# Atari_Controller.net
KiCad netlist of a schematic drawn in Altium Designer
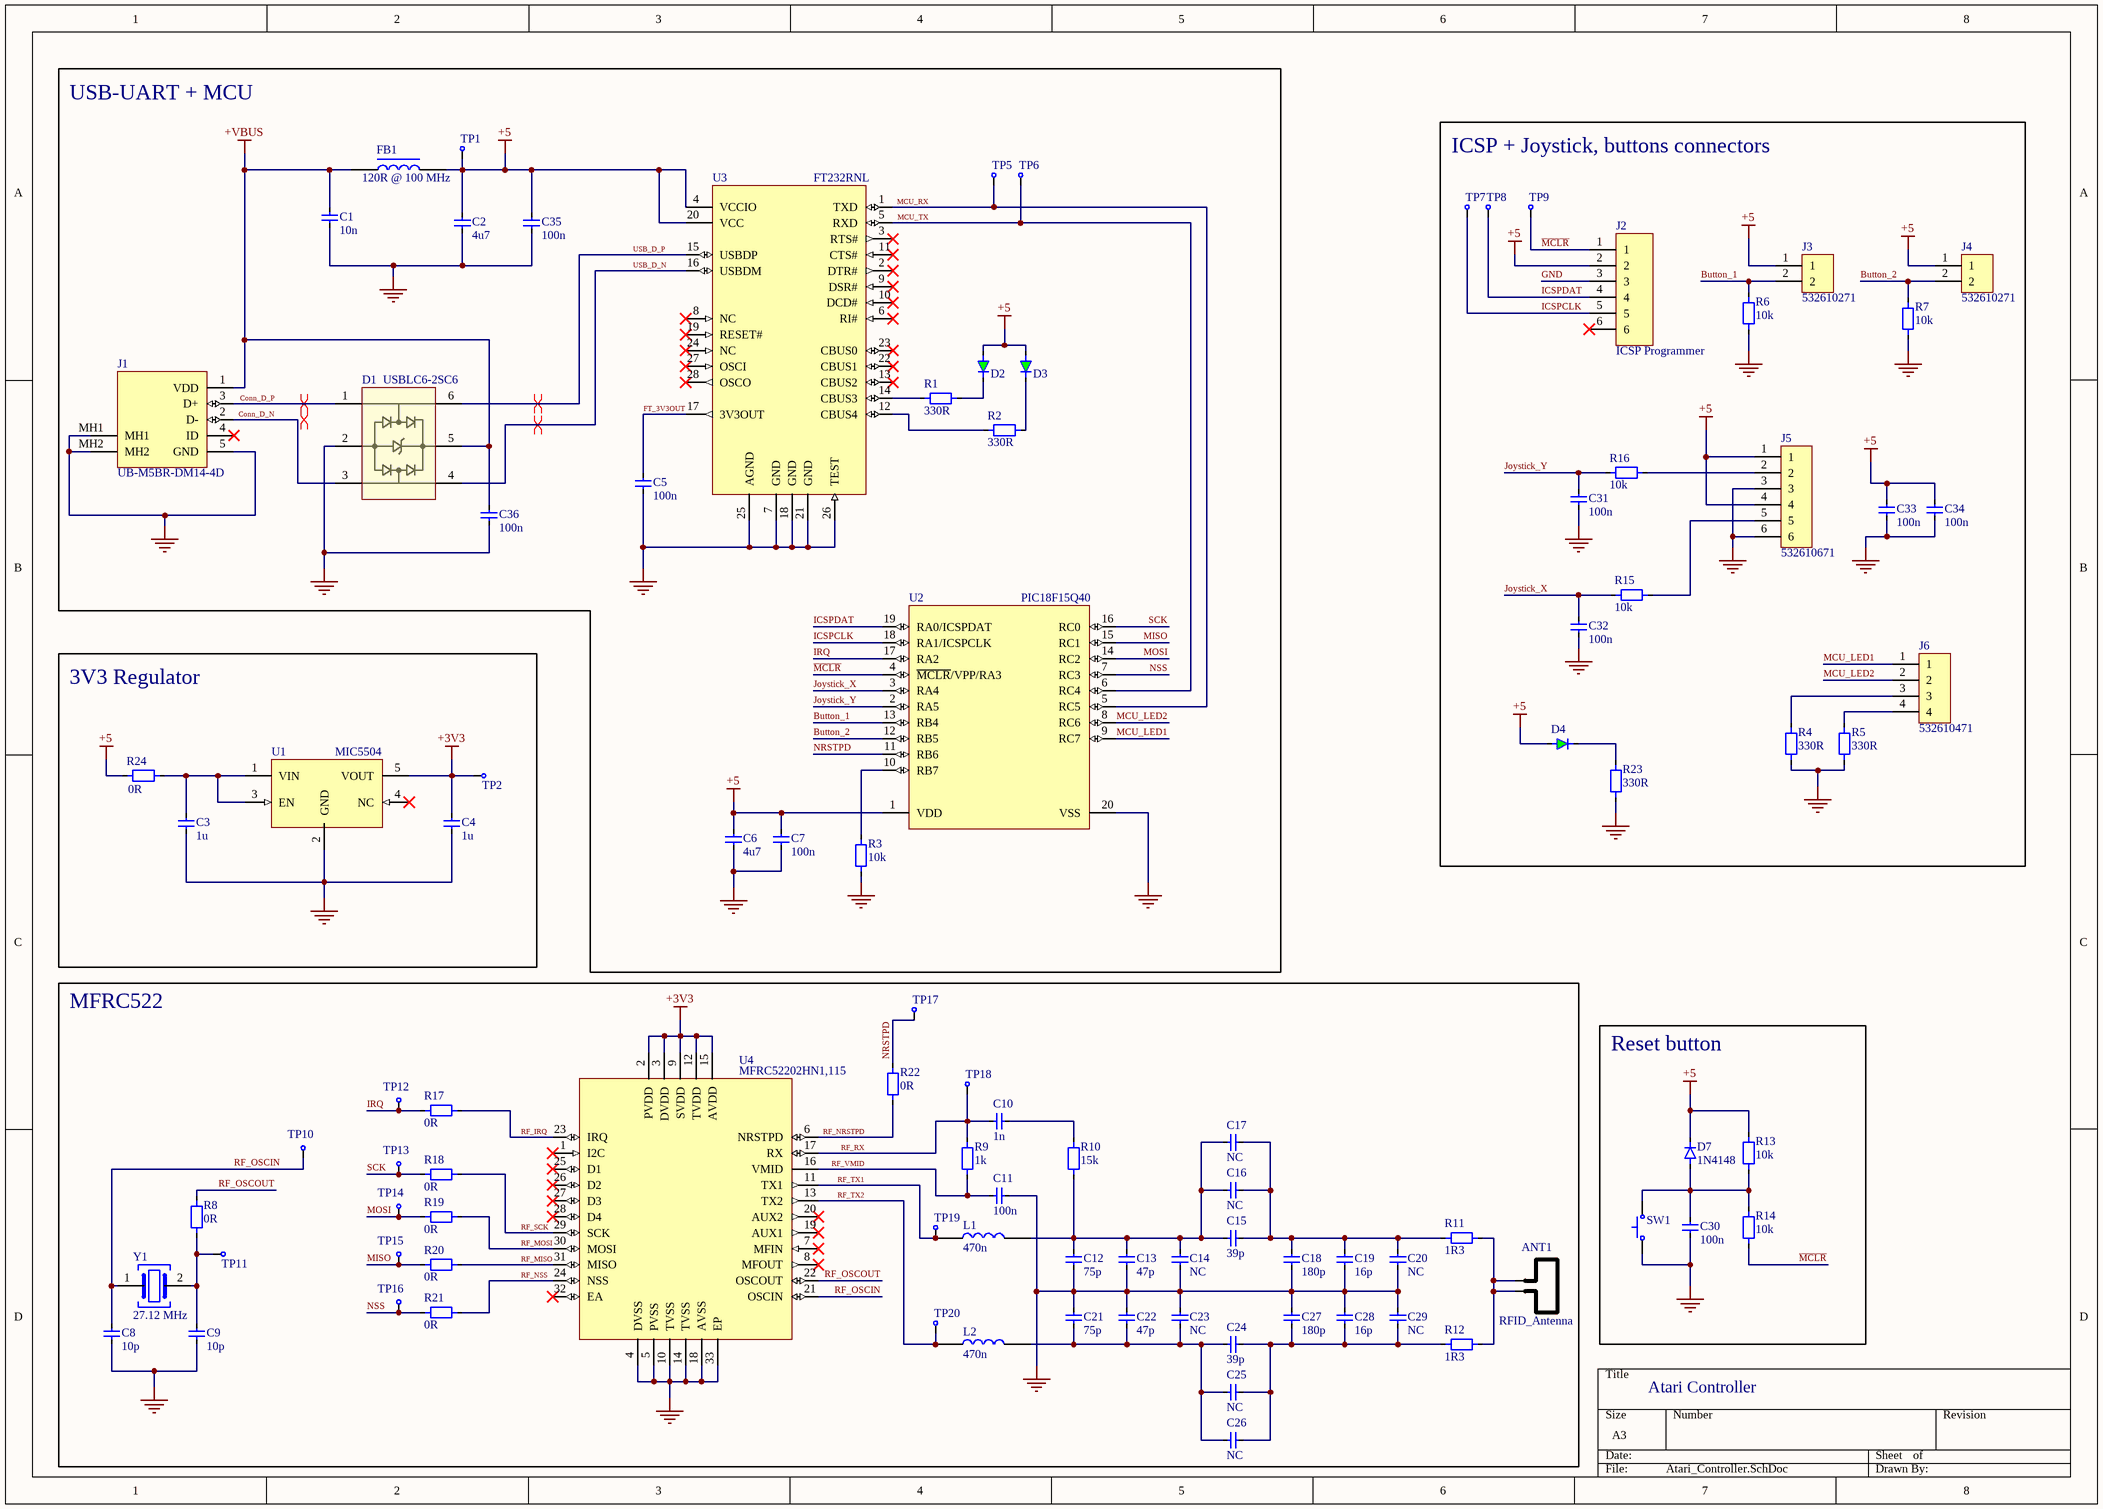
[diagram p0: Atari_Controller.SchDoc]

(export (version "E")
  (design (tool "Eeschema 10.0.6"))
  (components
    (comp (ref "ANT1")
      (value "RFID_Antenna")
      (footprint "RFID_Antenna")
      (description "Matching for MRFC522")
      (libsource (lib "Schematics_Connectors") (part "RFID_Antenna"))
    )
    (comp (ref "C1")
      (value "10n")
      (footprint "CAP_0603")
      (description "Capacitor SMD 0603 16V")
      (libsource (lib "Schematics_Passives") (part "CAP_0603_16V"))
    )
    (comp (ref "C2")
      (value "4u7")
      (footprint "CAP_0603")
      (description "Capacitor SMD 0603 16V")
      (libsource (lib "Schematics_Passives") (part "CAP_0603_16V"))
    )
    (comp (ref "C3")
      (value "1u")
      (footprint "CAP_0603")
      (description "Capacitor SMD 0603 16V")
      (libsource (lib "Schematics_Passives") (part "CAP_0603_16V"))
    )
    (comp (ref "C4")
      (value "1u")
      (footprint "CAP_0603")
      (description "Capacitor SMD 0603 16V")
      (libsource (lib "Schematics_Passives") (part "CAP_0603_16V"))
    )
    (comp (ref "C5")
      (value "100n")
      (footprint "CAP_0603")
      (description "Capacitor SMD 0603 10V")
      (libsource (lib "Schematics_Passives") (part "CAP_0603_10V"))
    )
    (comp (ref "C6")
      (value "4u7")
      (footprint "CAP_0603")
      (description "Capacitor SMD 0603 16V")
      (libsource (lib "Schematics_Passives") (part "CAP_0603_16V"))
    )
    (comp (ref "C7")
      (value "100n")
      (footprint "CAP_0603")
      (description "Capacitor SMD 0603 16V")
      (libsource (lib "Schematics_Passives") (part "CAP_0603_16V"))
    )
    (comp (ref "C8")
      (value "10p")
      (footprint "CAP_0603")
      (description "Capacitor SMD 0603 16V")
      (libsource (lib "Schematics_Passives") (part "CAP_0603_16V"))
    )
    (comp (ref "C9")
      (value "10p")
      (footprint "CAP_0603")
      (description "Capacitor SMD 0603 16V")
      (libsource (lib "Schematics_Passives") (part "CAP_0603_16V"))
    )
    (comp (ref "C10")
      (value "1n")
      (footprint "CAP_0603")
      (description "Capacitor SMD 0603 16V")
      (libsource (lib "Schematics_Passives") (part "CAP_0603_16V"))
    )
    (comp (ref "C11")
      (value "100n")
      (footprint "CAP_0603")
      (description "Capacitor SMD 0603 16V")
      (libsource (lib "Schematics_Passives") (part "CAP_0603_16V"))
    )
    (comp (ref "C12")
      (value "75p")
      (footprint "CAP_0603")
      (description "Capacitor SMD 0603 16V")
      (libsource (lib "Schematics_Passives") (part "CAP_0603_16V"))
    )
    (comp (ref "C13")
      (value "47p")
      (footprint "CAP_0603")
      (description "Capacitor SMD 0603 16V")
      (libsource (lib "Schematics_Passives") (part "CAP_0603_16V"))
    )
    (comp (ref "C14")
      (value "NC")
      (footprint "CAP_0603")
      (description "Capacitor SMD 0603 16V")
      (libsource (lib "Schematics_Passives") (part "CAP_0603_16V"))
    )
    (comp (ref "C15")
      (value "39p")
      (footprint "CAP_0603")
      (description "Capacitor SMD 0603 16V")
      (libsource (lib "Schematics_Passives") (part "CAP_0603_16V"))
    )
    (comp (ref "C16")
      (value "NC")
      (footprint "CAP_0603")
      (description "Capacitor SMD 0603 16V")
      (libsource (lib "Schematics_Passives") (part "CAP_0603_16V"))
    )
    (comp (ref "C17")
      (value "NC")
      (footprint "CAP_0603")
      (description "Capacitor SMD 0603 16V")
      (libsource (lib "Schematics_Passives") (part "CAP_0603_16V"))
    )
    (comp (ref "C18")
      (value "180p")
      (footprint "CAP_0603")
      (description "Capacitor SMD 0603 16V")
      (libsource (lib "Schematics_Passives") (part "CAP_0603_16V"))
    )
    (comp (ref "C19")
      (value "16p")
      (footprint "CAP_0603")
      (description "Capacitor SMD 0603 16V")
      (libsource (lib "Schematics_Passives") (part "CAP_0603_16V"))
    )
    (comp (ref "C20")
      (value "NC")
      (footprint "CAP_0603")
      (description "Capacitor SMD 0603 16V")
      (libsource (lib "Schematics_Passives") (part "CAP_0603_16V"))
    )
    (comp (ref "C21")
      (value "75p")
      (footprint "CAP_0603")
      (description "Capacitor SMD 0603 16V")
      (libsource (lib "Schematics_Passives") (part "CAP_0603_16V"))
    )
    (comp (ref "C22")
      (value "47p")
      (footprint "CAP_0603")
      (description "Capacitor SMD 0603 16V")
      (libsource (lib "Schematics_Passives") (part "CAP_0603_16V"))
    )
    (comp (ref "C23")
      (value "NC")
      (footprint "CAP_0603")
      (description "Capacitor SMD 0603 16V")
      (libsource (lib "Schematics_Passives") (part "CAP_0603_16V"))
    )
    (comp (ref "C24")
      (value "39p")
      (footprint "CAP_0603")
      (description "Capacitor SMD 0603 16V")
      (libsource (lib "Schematics_Passives") (part "CAP_0603_16V"))
    )
    (comp (ref "C25")
      (value "NC")
      (footprint "CAP_0603")
      (description "Capacitor SMD 0603 16V")
      (libsource (lib "Schematics_Passives") (part "CAP_0603_16V"))
    )
    (comp (ref "C26")
      (value "NC")
      (footprint "CAP_0603")
      (description "Capacitor SMD 0603 16V")
      (libsource (lib "Schematics_Passives") (part "CAP_0603_16V"))
    )
    (comp (ref "C27")
      (value "180p")
      (footprint "CAP_0603")
      (description "Capacitor SMD 0603 16V")
      (libsource (lib "Schematics_Passives") (part "CAP_0603_16V"))
    )
    (comp (ref "C28")
      (value "16p")
      (footprint "CAP_0603")
      (description "Capacitor SMD 0603 16V")
      (libsource (lib "Schematics_Passives") (part "CAP_0603_16V"))
    )
    (comp (ref "C29")
      (value "NC")
      (footprint "CAP_0603")
      (description "Capacitor SMD 0603 16V")
      (libsource (lib "Schematics_Passives") (part "CAP_0603_16V"))
    )
    (comp (ref "C30")
      (value "100n")
      (footprint "CAP_0603")
      (description "Capacitor SMD 0603 10V")
      (libsource (lib "Schematics_Passives") (part "CAP_0603_10V"))
    )
    (comp (ref "C31")
      (value "100n")
      (footprint "CAP_0603")
      (description "Capacitor SMD 0603 16V")
      (libsource (lib "Schematics_Passives") (part "CAP_0603_16V"))
    )
    (comp (ref "C32")
      (value "100n")
      (footprint "CAP_0603")
      (description "Capacitor SMD 0603 16V")
      (libsource (lib "Schematics_Passives") (part "CAP_0603_16V"))
    )
    (comp (ref "C33")
      (value "100n")
      (footprint "CAP_0603")
      (description "Capacitor SMD 0603 16V")
      (libsource (lib "Schematics_Passives") (part "CAP_0603_16V"))
    )
    (comp (ref "C34")
      (value "100n")
      (footprint "CAP_0603")
      (description "Capacitor SMD 0603 16V")
      (libsource (lib "Schematics_Passives") (part "CAP_0603_16V"))
    )
    (comp (ref "C35")
      (value "100n")
      (footprint "CAP_0603")
      (description "Capacitor SMD 0603 10V")
      (libsource (lib "Schematics_Passives") (part "CAP_0603_10V"))
    )
    (comp (ref "C36")
      (value "100n")
      (footprint "CAP_0603")
      (description "Capacitor SMD 0603 16V")
      (libsource (lib "Schematics_Passives") (part "CAP_0603_16V"))
    )
    (comp (ref "D1")
      (value "USBLC6-2SC6")
      (footprint "SOT-666")
      (description "ESD Suppressors / TVS Diodes ESD Protection Low Cap")
      (libsource (lib "Schematics_IC") (part "USBLC6-2SC6"))
    )
    (comp (ref "D2")
      (value "SMD-GREEN")
      (footprint "LED_0603")
      (description "LED SMD 0603")
      (libsource (lib "Schematics_Semiconductors") (part "LED_0603"))
    )
    (comp (ref "D3")
      (value "SMD-GREEN")
      (footprint "LED_0603")
      (description "LED SMD 0603")
      (libsource (lib "Schematics_Semiconductors") (part "LED_0603"))
    )
    (comp (ref "D4")
      (value "SMD-RED")
      (footprint "LED_0603")
      (description "LED SMD 0603")
      (libsource (lib "Schematics_Semiconductors") (part "LED_0603"))
    )
    (comp (ref "D7")
      (value "1N4148")
      (footprint "1N4148")
      (description "THT; 100V; 0,2A; Ifsm: 1A; DO35; Ufmax: 1V; 4ns")
      (libsource (lib "Schematics_Semiconductors") (part "1N4148"))
    )
    (comp (ref "FB1")
      (value "120R @ 100 MHz")
      (footprint "Ferrite_Bead_0603")
      (description "Ferrite Bead 0603")
      (libsource (lib "Schematics_Passives") (part "FERRITE_BEAD_0603"))
    )
    (comp (ref "J1")
      (value "UB-M5BR-DM14-4D")
      (footprint "USB-B-MINI")
      (libsource (lib "Schematics_Connectors") (part "USB-B-MINI"))
    )
    (comp (ref "J2")
      (value "ICSP Programmer")
      (footprint "6_pin_2.54")
      (description "6 pin male header 2.54mm")
      (libsource (lib "Schematics_Connectors") (part "6-pin header 2.54mm"))
    )
    (comp (ref "J3")
      (value "532610271")
      (footprint "Molex_Picoblade_2pin")
      (description "Zásuvka; kabel-pl.spoj; vidlice; PicoBlade™; 1,25mm; PIN: 2; SMT; 1A")
      (libsource (lib "Schematics_Connectors") (part "PicoBlade_2"))
    )
    (comp (ref "J4")
      (value "532610271")
      (footprint "Molex_Picoblade_2pin")
      (description "Zásuvka; kabel-pl.spoj; vidlice; PicoBlade™; 1,25mm; PIN: 2; SMT; 1A")
      (libsource (lib "Schematics_Connectors") (part "PicoBlade_2"))
    )
    (comp (ref "J5")
      (value "532610671")
      (footprint "Molex_Picoblade_6pin")
      (description "Zásuvka; kabel-pl.spoj; vidlice; PicoBlade™; 1,25mm; PIN: 6; SMT; 1A")
      (libsource (lib "Schematics_Connectors") (part "PicoBlade_6"))
    )
    (comp (ref "J6")
      (value "532610471")
      (footprint "MOLEX_PICOBLADE_4Pin")
      (description "Zásuvka; kabel-pl.spoj; vidlice; PicoBlade™; 1,25mm; PIN: 4; SMT; 1A")
      (libsource (lib "Schematics_Connectors") (part "PicoBlade_4"))
    )
    (comp (ref "L1")
      (value "470n")
      (footprint "IND_0603")
      (description "Inductor 0603 SMD")
      (libsource (lib "Schematics_Passives") (part "IND_0603"))
    )
    (comp (ref "L2")
      (value "470n")
      (footprint "IND_0603")
      (description "Inductor 0603 SMD")
      (libsource (lib "Schematics_Passives") (part "IND_0603"))
    )
    (comp (ref "R1")
      (value "330R")
      (footprint "RES_0603")
      (description "Resistor SMD 0603")
      (libsource (lib "Schematics_Passives") (part "RES_0603"))
    )
    (comp (ref "R2")
      (value "330R")
      (footprint "RES_0603")
      (description "Resistor SMD 0603")
      (libsource (lib "Schematics_Passives") (part "RES_0603"))
    )
    (comp (ref "R3")
      (value "10k")
      (footprint "RES_0603")
      (description "Resistor SMD 0603")
      (libsource (lib "Schematics_Passives") (part "RES_0603"))
    )
    (comp (ref "R4")
      (value "330R")
      (footprint "RES_0603")
      (description "Resistor SMD 0603")
      (libsource (lib "Schematics_Passives") (part "RES_0603"))
    )
    (comp (ref "R5")
      (value "330R")
      (footprint "RES_0603")
      (description "Resistor SMD 0603")
      (libsource (lib "Schematics_Passives") (part "RES_0603"))
    )
    (comp (ref "R6")
      (value "10k")
      (footprint "RES_0603")
      (description "Resistor SMD 0603")
      (libsource (lib "Schematics_Passives") (part "RES_0603"))
    )
    (comp (ref "R7")
      (value "10k")
      (footprint "RES_0603")
      (description "Resistor SMD 0603")
      (libsource (lib "Schematics_Passives") (part "RES_0603"))
    )
    (comp (ref "R8")
      (value "0R")
      (footprint "RES_0603")
      (description "Resistor SMD 0603")
      (libsource (lib "Schematics_Passives") (part "RES_0603"))
    )
    (comp (ref "R9")
      (value "1k")
      (footprint "RES_0603")
      (description "Resistor SMD 0603")
      (libsource (lib "Schematics_Passives") (part "RES_0603"))
    )
    (comp (ref "R10")
      (value "15k")
      (footprint "RES_0603")
      (description "Resistor SMD 0603")
      (libsource (lib "Schematics_Passives") (part "RES_0603"))
    )
    (comp (ref "R11")
      (value "1R3")
      (footprint "RES_0603")
      (description "Resistor SMD 0603")
      (libsource (lib "Schematics_Passives") (part "RES_0603"))
    )
    (comp (ref "R12")
      (value "1R3")
      (footprint "RES_0603")
      (description "Resistor SMD 0603")
      (libsource (lib "Schematics_Passives") (part "RES_0603"))
    )
    (comp (ref "R13")
      (value "10k")
      (footprint "RES_0603")
      (description "Resistor SMD 0603")
      (libsource (lib "Schematics_Passives") (part "RES_0603"))
    )
    (comp (ref "R14")
      (value "10k")
      (footprint "RES_0603")
      (description "Resistor SMD 0603")
      (libsource (lib "Schematics_Passives") (part "RES_0603"))
    )
    (comp (ref "R15")
      (value "10k")
      (footprint "RES_0603")
      (description "Resistor SMD 0603")
      (libsource (lib "Schematics_Passives") (part "RES_0603"))
    )
    (comp (ref "R16")
      (value "10k")
      (footprint "RES_0603")
      (description "Resistor SMD 0603")
      (libsource (lib "Schematics_Passives") (part "RES_0603"))
    )
    (comp (ref "R17")
      (value "0R")
      (footprint "RES_0603")
      (description "Resistor SMD 0603")
      (libsource (lib "Schematics_Passives") (part "RES_0603"))
    )
    (comp (ref "R18")
      (value "0R")
      (footprint "RES_0603")
      (description "Resistor SMD 0603")
      (libsource (lib "Schematics_Passives") (part "RES_0603"))
    )
    (comp (ref "R19")
      (value "0R")
      (footprint "RES_0603")
      (description "Resistor SMD 0603")
      (libsource (lib "Schematics_Passives") (part "RES_0603"))
    )
    (comp (ref "R20")
      (value "0R")
      (footprint "RES_0603")
      (description "Resistor SMD 0603")
      (libsource (lib "Schematics_Passives") (part "RES_0603"))
    )
    (comp (ref "R21")
      (value "0R")
      (footprint "RES_0603")
      (description "Resistor SMD 0603")
      (libsource (lib "Schematics_Passives") (part "RES_0603"))
    )
    (comp (ref "R22")
      (value "0R")
      (footprint "RES_0603")
      (description "Resistor SMD 0603")
      (libsource (lib "Schematics_Passives") (part "RES_0603"))
    )
    (comp (ref "R23")
      (value "330R")
      (footprint "RES_0603")
      (description "Resistor SMD 0603")
      (libsource (lib "Schematics_Passives") (part "RES_0603"))
    )
    (comp (ref "R24")
      (value "0R")
      (footprint "RES_0603")
      (description "Resistor SMD 0603")
      (libsource (lib "Schematics_Passives") (part "RES_0603"))
    )
    (comp (ref "SW1")
      (value "SPST_Switch")
      (footprint "Tactile_Switch_4.5x4.5")
      (description "SPST-NO Tactile Switch 4.5x4.5")
      (libsource (lib "Schematics_Connectors") (part "SPST_Switch"))
    )
    (comp (ref "TP1")
      (value "TestPoint")
      (footprint "Pad_2.5mm")
      (libsource (lib "Schematics_Connectors") (part "TestPoint"))
    )
    (comp (ref "TP2")
      (value "TestPoint")
      (footprint "Pad_2.5mm")
      (libsource (lib "Schematics_Connectors") (part "TestPoint"))
    )
    (comp (ref "TP5")
      (value "TestPoint")
      (footprint "Pad_2.5mm")
      (libsource (lib "Schematics_Connectors") (part "TestPoint"))
    )
    (comp (ref "TP6")
      (value "TestPoint")
      (footprint "Pad_2.5mm")
      (libsource (lib "Schematics_Connectors") (part "TestPoint"))
    )
    (comp (ref "TP7")
      (value "TestPoint")
      (footprint "Pad_2.5mm")
      (libsource (lib "Schematics_Connectors") (part "TestPoint"))
    )
    (comp (ref "TP8")
      (value "TestPoint")
      (footprint "Pad_2.5mm")
      (libsource (lib "Schematics_Connectors") (part "TestPoint"))
    )
    (comp (ref "TP9")
      (value "TestPoint")
      (footprint "Pad_2.5mm")
      (libsource (lib "Schematics_Connectors") (part "TestPoint"))
    )
    (comp (ref "TP10")
      (value "TestPoint")
      (footprint "Pad_2.5mm")
      (libsource (lib "Schematics_Connectors") (part "TestPoint"))
    )
    (comp (ref "TP11")
      (value "TestPoint")
      (footprint "Pad_2.5mm")
      (libsource (lib "Schematics_Connectors") (part "TestPoint"))
    )
    (comp (ref "TP12")
      (value "TestPoint")
      (footprint "Pad_2.5mm")
      (libsource (lib "Schematics_Connectors") (part "TestPoint"))
    )
    (comp (ref "TP13")
      (value "TestPoint")
      (footprint "Pad_2.5mm")
      (libsource (lib "Schematics_Connectors") (part "TestPoint"))
    )
    (comp (ref "TP14")
      (value "TestPoint")
      (footprint "Pad_2.5mm")
      (libsource (lib "Schematics_Connectors") (part "TestPoint"))
    )
    (comp (ref "TP15")
      (value "TestPoint")
      (footprint "Pad_2.5mm")
      (libsource (lib "Schematics_Connectors") (part "TestPoint"))
    )
    (comp (ref "TP16")
      (value "TestPoint")
      (footprint "Pad_2.5mm")
      (libsource (lib "Schematics_Connectors") (part "TestPoint"))
    )
    (comp (ref "TP17")
      (value "TestPoint")
      (footprint "Pad_2.5mm")
      (libsource (lib "Schematics_Connectors") (part "TestPoint"))
    )
    (comp (ref "TP18")
      (value "TestPoint")
      (footprint "Pad_2.5mm")
      (libsource (lib "Schematics_Connectors") (part "TestPoint"))
    )
    (comp (ref "TP19")
      (value "TestPoint")
      (footprint "Pad_2.5mm")
      (libsource (lib "Schematics_Connectors") (part "TestPoint"))
    )
    (comp (ref "TP20")
      (value "TestPoint")
      (footprint "Pad_2.5mm")
      (libsource (lib "Schematics_Connectors") (part "TestPoint"))
    )
    (comp (ref "U1")
      (value "MIC5504")
      (footprint "SOT-23-5")
      (description "LDO regulator 3.3V")
      (libsource (lib "Schematics_IC") (part "MIC5504-3.3YM5-TR"))
    )
    (comp (ref "U2")
      (value "PIC18F15Q40")
      (footprint "SOP20")
      (description "PIC18F04/05/14/15Q40 14/20-Pin, Low-Power, High-Performance Microcontroller")
      (libsource (lib "Schematics_IC") (part "PIC18F15Q40"))
    )
    (comp (ref "U3")
      (value "FT232RNL")
      (footprint "SOP65P780X200-28N")
      (description "USB Interface IC USB Full Speed to Serial UART IC, Includes Oscillator and EEPROM, SSOP-28")
      (libsource (lib "Schematics_IC") (part "FT232RNL"))
    )
    (comp (ref "U4")
      (value "MFRC52202HN1,115")
      (footprint "PQFN50P500X500X100_HS-33N")
      (description "NFC/RFID Tags & Transponders Standard performance MIFARE and NTAG frontend")
      (libsource (lib "Schematics_IC") (part "MFRC52202HN1,115"))
    )
    (comp (ref "Y1")
      (value "27.12 MHz")
      (footprint "CrystalOscillator")
      (description "Crystal oscillator")
      (libsource (lib "Schematics_IC") (part "Crystal_Oscillator"))
    )
  )
  (nets
    (net (code "1") (name "+3V3") (class "Default")
      (node (ref "C4") (pin "2") (pinfunction "2_2") (pintype "passive"))
      (node (ref "TP2") (pin "1") (pinfunction "1_1") (pintype "passive"))
      (node (ref "U1") (pin "5") (pinfunction "VOUT_5") (pintype "power_in"))
      (node (ref "U4") (pin "12") (pinfunction "TVDD_12") (pintype "power_in"))
      (node (ref "U4") (pin "15") (pinfunction "AVDD_15") (pintype "power_in"))
      (node (ref "U4") (pin "2") (pinfunction "PVDD_2") (pintype "power_in"))
      (node (ref "U4") (pin "3") (pinfunction "DVDD_3") (pintype "power_in"))
      (node (ref "U4") (pin "9") (pinfunction "SVDD_9") (pintype "power_in"))
    )
    (net (code "2") (name "+5") (class "Default")
      (node (ref "C2") (pin "2") (pinfunction "2_2") (pintype "passive"))
      (node (ref "C33") (pin "2") (pinfunction "2_2") (pintype "passive"))
      (node (ref "C34") (pin "2") (pinfunction "2_2") (pintype "passive"))
      (node (ref "C35") (pin "2") (pinfunction "2_2") (pintype "passive"))
      (node (ref "C6") (pin "2") (pinfunction "2_2") (pintype "passive"))
      (node (ref "C7") (pin "2") (pinfunction "2_2") (pintype "passive"))
      (node (ref "D2") (pin "2") (pinfunction "2_2") (pintype "passive"))
      (node (ref "D3") (pin "2") (pinfunction "2_2") (pintype "passive"))
      (node (ref "D4") (pin "2") (pinfunction "2_2") (pintype "passive"))
      (node (ref "D7") (pin "1") (pinfunction "1_1") (pintype "passive"))
      (node (ref "FB1") (pin "2") (pinfunction "2_2") (pintype "passive"))
      (node (ref "J2") (pin "2") (pinfunction "2_2") (pintype "passive"))
      (node (ref "J3") (pin "1") (pinfunction "1_1") (pintype "passive"))
      (node (ref "J4") (pin "1") (pinfunction "1_1") (pintype "passive"))
      (node (ref "J5") (pin "1") (pinfunction "1_1") (pintype "passive"))
      (node (ref "J5") (pin "4") (pinfunction "4_4") (pintype "passive"))
      (node (ref "R13") (pin "2") (pinfunction "2_2") (pintype "passive"))
      (node (ref "R24") (pin "1") (pinfunction "1_1") (pintype "passive"))
      (node (ref "TP1") (pin "1") (pinfunction "1_1") (pintype "passive"))
      (node (ref "U2") (pin "1") (pinfunction "VDD_1") (pintype "power_in"))
      (node (ref "U3") (pin "20") (pinfunction "VCC_20") (pintype "power_in"))
      (node (ref "U3") (pin "4") (pinfunction "VCCIO_4") (pintype "power_in"))
    )
    (net (code "3") (name "+VBUS") (class "Default")
      (node (ref "C1") (pin "2") (pinfunction "2_2") (pintype "passive"))
      (node (ref "C36") (pin "2") (pinfunction "2_2") (pintype "passive"))
      (node (ref "D1") (pin "5") (pinfunction "VBUS_5") (pintype "passive"))
      (node (ref "FB1") (pin "1") (pinfunction "1_1") (pintype "passive"))
      (node (ref "J1") (pin "1") (pinfunction "VDD_1") (pintype "power_in"))
    )
    (net (code "4") (name "/Button_1") (class "Default")
      (node (ref "J3") (pin "2") (pinfunction "2_2") (pintype "passive"))
      (node (ref "R6") (pin "2") (pinfunction "2_2") (pintype "passive"))
      (node (ref "U2") (pin "13") (pinfunction "RB4_13") (pintype "bidirectional"))
    )
    (net (code "5") (name "/Button_2") (class "Default")
      (node (ref "J4") (pin "2") (pinfunction "2_2") (pintype "passive"))
      (node (ref "R7") (pin "2") (pinfunction "2_2") (pintype "passive"))
      (node (ref "U2") (pin "12") (pinfunction "RB5_12") (pintype "bidirectional"))
    )
    (net (code "6") (name "/Conn_D_N") (class "Default")
      (node (ref "D1") (pin "3") (pinfunction "I/O_2_3") (pintype "passive"))
      (node (ref "J1") (pin "2") (pinfunction "D-_2") (pintype "bidirectional"))
    )
    (net (code "7") (name "/Conn_D_P") (class "Default")
      (node (ref "D1") (pin "1") (pinfunction "I/O_1_1") (pintype "passive"))
      (node (ref "J1") (pin "3") (pinfunction "D+_3") (pintype "bidirectional"))
    )
    (net (code "8") (name "/FT_3V3OUT") (class "Default")
      (node (ref "C5") (pin "2") (pinfunction "2_2") (pintype "passive"))
      (node (ref "U3") (pin "17") (pinfunction "3V3OUT_17") (pintype "output"))
    )
    (net (code "9") (name "/ICSPCLK") (class "Default")
      (node (ref "J2") (pin "5") (pinfunction "5_5") (pintype "passive"))
      (node (ref "TP7") (pin "1") (pinfunction "1_1") (pintype "passive"))
      (node (ref "U2") (pin "18") (pinfunction "RA1/ICSPCLK_18") (pintype "bidirectional"))
    )
    (net (code "10") (name "/ICSPDAT") (class "Default")
      (node (ref "J2") (pin "4") (pinfunction "4_4") (pintype "passive"))
      (node (ref "TP8") (pin "1") (pinfunction "1_1") (pintype "passive"))
      (node (ref "U2") (pin "19") (pinfunction "RA0/ICSPDAT_19") (pintype "bidirectional"))
    )
    (net (code "11") (name "/IRQ") (class "Default")
      (node (ref "R17") (pin "1") (pinfunction "1_1") (pintype "passive"))
      (node (ref "TP12") (pin "1") (pinfunction "1_1") (pintype "passive"))
      (node (ref "U2") (pin "17") (pinfunction "RA2_17") (pintype "bidirectional"))
    )
    (net (code "12") (name "/Joystick_X") (class "Default")
      (node (ref "C32") (pin "2") (pinfunction "2_2") (pintype "passive"))
      (node (ref "R15") (pin "1") (pinfunction "1_1") (pintype "passive"))
      (node (ref "U2") (pin "3") (pinfunction "RA4_3") (pintype "bidirectional"))
    )
    (net (code "13") (name "/Joystick_Y") (class "Default")
      (node (ref "C31") (pin "2") (pinfunction "2_2") (pintype "passive"))
      (node (ref "R16") (pin "1") (pinfunction "1_1") (pintype "passive"))
      (node (ref "U2") (pin "2") (pinfunction "RA5_2") (pintype "bidirectional"))
    )
    (net (code "14") (name "/MCU_LED1") (class "Default")
      (node (ref "J6") (pin "1") (pinfunction "1_1") (pintype "passive"))
      (node (ref "U2") (pin "9") (pinfunction "RC7_9") (pintype "bidirectional"))
    )
    (net (code "15") (name "/MCU_LED2") (class "Default")
      (node (ref "J6") (pin "2") (pinfunction "2_2") (pintype "passive"))
      (node (ref "U2") (pin "8") (pinfunction "RC6_8") (pintype "bidirectional"))
    )
    (net (code "16") (name "/MCU_RX") (class "Default")
      (node (ref "TP5") (pin "1") (pinfunction "1_1") (pintype "passive"))
      (node (ref "U2") (pin "5") (pinfunction "RC5_5") (pintype "bidirectional"))
      (node (ref "U3") (pin "1") (pinfunction "TXD_1") (pintype "bidirectional"))
    )
    (net (code "17") (name "/MCU_TX") (class "Default")
      (node (ref "TP6") (pin "1") (pinfunction "1_1") (pintype "passive"))
      (node (ref "U2") (pin "6") (pinfunction "RC4_6") (pintype "bidirectional"))
      (node (ref "U3") (pin "5") (pinfunction "RXD_5") (pintype "bidirectional"))
    )
    (net (code "18") (name "/MISO") (class "Default")
      (node (ref "R20") (pin "1") (pinfunction "1_1") (pintype "passive"))
      (node (ref "TP15") (pin "1") (pinfunction "1_1") (pintype "passive"))
      (node (ref "U2") (pin "15") (pinfunction "RC1_15") (pintype "bidirectional"))
    )
    (net (code "19") (name "/MOSI") (class "Default")
      (node (ref "R19") (pin "1") (pinfunction "1_1") (pintype "passive"))
      (node (ref "TP14") (pin "1") (pinfunction "1_1") (pintype "passive"))
      (node (ref "U2") (pin "14") (pinfunction "RC2_14") (pintype "bidirectional"))
    )
    (net (code "20") (name "/NRSTPD") (class "Default")
      (node (ref "R22") (pin "2") (pinfunction "2_2") (pintype "passive"))
      (node (ref "TP17") (pin "1") (pinfunction "1_1") (pintype "passive"))
      (node (ref "U2") (pin "11") (pinfunction "RB6_11") (pintype "bidirectional"))
    )
    (net (code "21") (name "/NSS") (class "Default")
      (node (ref "R21") (pin "1") (pinfunction "1_1") (pintype "passive"))
      (node (ref "TP16") (pin "1") (pinfunction "1_1") (pintype "passive"))
      (node (ref "U2") (pin "7") (pinfunction "RC3_7") (pintype "bidirectional"))
    )
    (net (code "22") (name "/RF_IRQ") (class "Default")
      (node (ref "R17") (pin "2") (pinfunction "2_2") (pintype "passive"))
      (node (ref "U4") (pin "23") (pinfunction "IRQ_23") (pintype "bidirectional"))
    )
    (net (code "23") (name "/RF_MISO") (class "Default")
      (node (ref "R20") (pin "2") (pinfunction "2_2") (pintype "passive"))
      (node (ref "U4") (pin "31") (pinfunction "MISO_31") (pintype "bidirectional"))
    )
    (net (code "24") (name "/RF_MOSI") (class "Default")
      (node (ref "R19") (pin "2") (pinfunction "2_2") (pintype "passive"))
      (node (ref "U4") (pin "30") (pinfunction "MOSI_30") (pintype "bidirectional"))
    )
    (net (code "25") (name "/RF_NRSTPD") (class "Default")
      (node (ref "R22") (pin "1") (pinfunction "1_1") (pintype "passive"))
      (node (ref "U4") (pin "6") (pinfunction "NRSTPD_6") (pintype "bidirectional"))
    )
    (net (code "26") (name "/RF_NSS") (class "Default")
      (node (ref "R21") (pin "2") (pinfunction "2_2") (pintype "passive"))
      (node (ref "U4") (pin "24") (pinfunction "NSS_24") (pintype "bidirectional"))
    )
    (net (code "27") (name "/RF_OSCIN") (class "Default")
      (node (ref "C8") (pin "2") (pinfunction "2_2") (pintype "passive"))
      (node (ref "TP10") (pin "1") (pinfunction "1_1") (pintype "passive"))
      (node (ref "U4") (pin "21") (pinfunction "OSCIN_21") (pintype "bidirectional"))
      (node (ref "Y1") (pin "1") (pinfunction "1_1") (pintype "passive"))
    )
    (net (code "28") (name "/RF_OSCOUT") (class "Default")
      (node (ref "R8") (pin "2") (pinfunction "2_2") (pintype "passive"))
      (node (ref "U4") (pin "22") (pinfunction "OSCOUT_22") (pintype "bidirectional"))
    )
    (net (code "29") (name "/RF_RX") (class "Default")
      (node (ref "C10") (pin "2") (pinfunction "2_2") (pintype "passive"))
      (node (ref "R9") (pin "2") (pinfunction "2_2") (pintype "passive"))
      (node (ref "TP18") (pin "1") (pinfunction "1_1") (pintype "passive"))
      (node (ref "U4") (pin "17") (pinfunction "RX_17") (pintype "bidirectional"))
    )
    (net (code "30") (name "/RF_SCK") (class "Default")
      (node (ref "R18") (pin "2") (pinfunction "2_2") (pintype "passive"))
      (node (ref "U4") (pin "29") (pinfunction "SCK_29") (pintype "bidirectional"))
    )
    (net (code "31") (name "/RF_TX1") (class "Default")
      (node (ref "L1") (pin "1") (pinfunction "1_1") (pintype "passive"))
      (node (ref "TP19") (pin "1") (pinfunction "1_1") (pintype "passive"))
      (node (ref "U4") (pin "11") (pinfunction "TX1_11") (pintype "output"))
    )
    (net (code "32") (name "/RF_TX2") (class "Default")
      (node (ref "L2") (pin "1") (pinfunction "1_1") (pintype "passive"))
      (node (ref "TP20") (pin "1") (pinfunction "1_1") (pintype "passive"))
      (node (ref "U4") (pin "13") (pinfunction "TX2_13") (pintype "output"))
    )
    (net (code "33") (name "/RF_VMID") (class "Default")
      (node (ref "C11") (pin "1") (pinfunction "1_1") (pintype "passive"))
      (node (ref "R9") (pin "1") (pinfunction "1_1") (pintype "passive"))
      (node (ref "U4") (pin "16") (pinfunction "VMID_16") (pintype "power_in"))
    )
    (net (code "34") (name "/SCK") (class "Default")
      (node (ref "R18") (pin "1") (pinfunction "1_1") (pintype "passive"))
      (node (ref "TP13") (pin "1") (pinfunction "1_1") (pintype "passive"))
      (node (ref "U2") (pin "16") (pinfunction "RC0_16") (pintype "bidirectional"))
    )
    (net (code "35") (name "/USB_D_N") (class "Default")
      (node (ref "D1") (pin "4") (pinfunction "I/O_3_4") (pintype "passive"))
      (node (ref "U3") (pin "16") (pinfunction "USBDM_16") (pintype "bidirectional"))
    )
    (net (code "36") (name "/USB_D_P") (class "Default")
      (node (ref "D1") (pin "6") (pinfunction "I/O_4_6") (pintype "passive"))
      (node (ref "U3") (pin "15") (pinfunction "USBDP_15") (pintype "bidirectional"))
    )
    (net (code "37") (name "/~{MCLR}") (class "Default")
      (node (ref "J2") (pin "1") (pinfunction "1_1") (pintype "passive"))
      (node (ref "R14") (pin "1") (pinfunction "1_1") (pintype "passive"))
      (node (ref "TP9") (pin "1") (pinfunction "1_1") (pintype "passive"))
      (node (ref "U2") (pin "4") (pinfunction "~{MCLR}/VPP/RA3_4") (pintype "bidirectional"))
    )
    (net (code "38") (name "GND") (class "Default")
      (node (ref "C1") (pin "1") (pinfunction "1_1") (pintype "passive"))
      (node (ref "C11") (pin "2") (pinfunction "2_2") (pintype "passive"))
      (node (ref "C12") (pin "1") (pinfunction "1_1") (pintype "passive"))
      (node (ref "C13") (pin "1") (pinfunction "1_1") (pintype "passive"))
      (node (ref "C14") (pin "1") (pinfunction "1_1") (pintype "passive"))
      (node (ref "C18") (pin "1") (pinfunction "1_1") (pintype "passive"))
      (node (ref "C19") (pin "1") (pinfunction "1_1") (pintype "passive"))
      (node (ref "C2") (pin "1") (pinfunction "1_1") (pintype "passive"))
      (node (ref "C20") (pin "1") (pinfunction "1_1") (pintype "passive"))
      (node (ref "C21") (pin "2") (pinfunction "2_2") (pintype "passive"))
      (node (ref "C22") (pin "2") (pinfunction "2_2") (pintype "passive"))
      (node (ref "C23") (pin "2") (pinfunction "2_2") (pintype "passive"))
      (node (ref "C27") (pin "2") (pinfunction "2_2") (pintype "passive"))
      (node (ref "C28") (pin "2") (pinfunction "2_2") (pintype "passive"))
      (node (ref "C29") (pin "2") (pinfunction "2_2") (pintype "passive"))
      (node (ref "C3") (pin "1") (pinfunction "1_1") (pintype "passive"))
      (node (ref "C30") (pin "1") (pinfunction "1_1") (pintype "passive"))
      (node (ref "C31") (pin "1") (pinfunction "1_1") (pintype "passive"))
      (node (ref "C32") (pin "1") (pinfunction "1_1") (pintype "passive"))
      (node (ref "C33") (pin "1") (pinfunction "1_1") (pintype "passive"))
      (node (ref "C34") (pin "1") (pinfunction "1_1") (pintype "passive"))
      (node (ref "C35") (pin "1") (pinfunction "1_1") (pintype "passive"))
      (node (ref "C36") (pin "1") (pinfunction "1_1") (pintype "passive"))
      (node (ref "C4") (pin "1") (pinfunction "1_1") (pintype "passive"))
      (node (ref "C5") (pin "1") (pinfunction "1_1") (pintype "passive"))
      (node (ref "C6") (pin "1") (pinfunction "1_1") (pintype "passive"))
      (node (ref "C7") (pin "1") (pinfunction "1_1") (pintype "passive"))
      (node (ref "C8") (pin "1") (pinfunction "1_1") (pintype "passive"))
      (node (ref "C9") (pin "1") (pinfunction "1_1") (pintype "passive"))
      (node (ref "D1") (pin "2") (pinfunction "GND_2") (pintype "passive"))
      (node (ref "J1") (pin "5") (pinfunction "GND_5") (pintype "power_in"))
      (node (ref "J1") (pin "MH1") (pinfunction "MH1_MH1") (pintype "passive"))
      (node (ref "J1") (pin "MH2") (pinfunction "MH2_MH2") (pintype "passive"))
      (node (ref "J2") (pin "3") (pinfunction "3_3") (pintype "passive"))
      (node (ref "J5") (pin "3") (pinfunction "3_3") (pintype "passive"))
      (node (ref "J5") (pin "6") (pinfunction "6_6") (pintype "passive"))
      (node (ref "R23") (pin "1") (pinfunction "1_1") (pintype "passive"))
      (node (ref "R3") (pin "1") (pinfunction "1_1") (pintype "passive"))
      (node (ref "R4") (pin "1") (pinfunction "1_1") (pintype "passive"))
      (node (ref "R5") (pin "1") (pinfunction "1_1") (pintype "passive"))
      (node (ref "R6") (pin "1") (pinfunction "1_1") (pintype "passive"))
      (node (ref "R7") (pin "1") (pinfunction "1_1") (pintype "passive"))
      (node (ref "SW1") (pin "1") (pinfunction "1_1") (pintype "passive"))
      (node (ref "U1") (pin "2") (pinfunction "GND_2") (pintype "power_in"))
      (node (ref "U2") (pin "20") (pinfunction "VSS_20") (pintype "power_in"))
      (node (ref "U3") (pin "18") (pinfunction "GND_18") (pintype "power_in"))
      (node (ref "U3") (pin "21") (pinfunction "GND_21") (pintype "power_in"))
      (node (ref "U3") (pin "25") (pinfunction "AGND_25") (pintype "power_in"))
      (node (ref "U3") (pin "26") (pinfunction "TEST_26") (pintype "input"))
      (node (ref "U3") (pin "7") (pinfunction "GND_7") (pintype "power_in"))
      (node (ref "U4") (pin "10") (pinfunction "TVSS_10") (pintype "power_in"))
      (node (ref "U4") (pin "14") (pinfunction "TVSS_14") (pintype "power_in"))
      (node (ref "U4") (pin "18") (pinfunction "AVSS_18") (pintype "power_in"))
      (node (ref "U4") (pin "33") (pinfunction "EP_33") (pintype "power_in"))
      (node (ref "U4") (pin "4") (pinfunction "DVSS_4") (pintype "power_in"))
      (node (ref "U4") (pin "5") (pinfunction "PVSS_5") (pintype "power_in"))
    )
    (net (code "39") (name "Net-(ANT1-Pad1)") (class "Default")
      (node (ref "ANT1") (pin "1") (pinfunction "1_1") (pintype "passive"))
      (node (ref "ANT1") (pin "2") (pinfunction "2_2") (pintype "passive"))
      (node (ref "R11") (pin "1") (pinfunction "1_1") (pintype "passive"))
      (node (ref "R12") (pin "2") (pinfunction "2_2") (pintype "passive"))
    )
    (net (code "40") (name "Net-(C9-Pad2)") (class "Default")
      (node (ref "C9") (pin "2") (pinfunction "2_2") (pintype "passive"))
      (node (ref "R8") (pin "1") (pinfunction "1_1") (pintype "passive"))
      (node (ref "TP11") (pin "1") (pinfunction "1_1") (pintype "passive"))
      (node (ref "Y1") (pin "2") (pinfunction "2_2") (pintype "passive"))
    )
    (net (code "41") (name "Net-(C10-Pad1)") (class "Default")
      (node (ref "C10") (pin "1") (pinfunction "1_1") (pintype "passive"))
      (node (ref "R10") (pin "2") (pinfunction "2_2") (pintype "passive"))
    )
    (net (code "42") (name "Net-(C12-Pad2)") (class "Default")
      (node (ref "C12") (pin "2") (pinfunction "2_2") (pintype "passive"))
      (node (ref "C13") (pin "2") (pinfunction "2_2") (pintype "passive"))
      (node (ref "C14") (pin "2") (pinfunction "2_2") (pintype "passive"))
      (node (ref "C15") (pin "1") (pinfunction "1_1") (pintype "passive"))
      (node (ref "C16") (pin "1") (pinfunction "1_1") (pintype "passive"))
      (node (ref "C17") (pin "1") (pinfunction "1_1") (pintype "passive"))
      (node (ref "L1") (pin "2") (pinfunction "2_2") (pintype "passive"))
      (node (ref "R10") (pin "1") (pinfunction "1_1") (pintype "passive"))
    )
    (net (code "43") (name "Net-(C15-Pad2)") (class "Default")
      (node (ref "C15") (pin "2") (pinfunction "2_2") (pintype "passive"))
      (node (ref "C16") (pin "2") (pinfunction "2_2") (pintype "passive"))
      (node (ref "C17") (pin "2") (pinfunction "2_2") (pintype "passive"))
      (node (ref "C18") (pin "2") (pinfunction "2_2") (pintype "passive"))
      (node (ref "C19") (pin "2") (pinfunction "2_2") (pintype "passive"))
      (node (ref "C20") (pin "2") (pinfunction "2_2") (pintype "passive"))
      (node (ref "R11") (pin "2") (pinfunction "2_2") (pintype "passive"))
    )
    (net (code "44") (name "Net-(C21-Pad1)") (class "Default")
      (node (ref "C21") (pin "1") (pinfunction "1_1") (pintype "passive"))
      (node (ref "C22") (pin "1") (pinfunction "1_1") (pintype "passive"))
      (node (ref "C23") (pin "1") (pinfunction "1_1") (pintype "passive"))
      (node (ref "C24") (pin "1") (pinfunction "1_1") (pintype "passive"))
      (node (ref "C25") (pin "1") (pinfunction "1_1") (pintype "passive"))
      (node (ref "C26") (pin "1") (pinfunction "1_1") (pintype "passive"))
      (node (ref "L2") (pin "2") (pinfunction "2_2") (pintype "passive"))
    )
    (net (code "45") (name "Net-(C24-Pad2)") (class "Default")
      (node (ref "C24") (pin "2") (pinfunction "2_2") (pintype "passive"))
      (node (ref "C25") (pin "2") (pinfunction "2_2") (pintype "passive"))
      (node (ref "C26") (pin "2") (pinfunction "2_2") (pintype "passive"))
      (node (ref "C27") (pin "1") (pinfunction "1_1") (pintype "passive"))
      (node (ref "C28") (pin "1") (pinfunction "1_1") (pintype "passive"))
      (node (ref "C29") (pin "1") (pinfunction "1_1") (pintype "passive"))
      (node (ref "R12") (pin "1") (pinfunction "1_1") (pintype "passive"))
    )
    (net (code "46") (name "Net-(C30-Pad2)") (class "Default")
      (node (ref "C30") (pin "2") (pinfunction "2_2") (pintype "passive"))
      (node (ref "D7") (pin "2") (pinfunction "2_2") (pintype "passive"))
      (node (ref "R13") (pin "1") (pinfunction "1_1") (pintype "passive"))
      (node (ref "R14") (pin "2") (pinfunction "2_2") (pintype "passive"))
      (node (ref "SW1") (pin "2") (pinfunction "2_2") (pintype "passive"))
    )
    (net (code "47") (name "Net-(D2-Pad1)") (class "Default")
      (node (ref "D2") (pin "1") (pinfunction "1_1") (pintype "passive"))
      (node (ref "R1") (pin "2") (pinfunction "2_2") (pintype "passive"))
    )
    (net (code "48") (name "Net-(D3-Pad1)") (class "Default")
      (node (ref "D3") (pin "1") (pinfunction "1_1") (pintype "passive"))
      (node (ref "R2") (pin "2") (pinfunction "2_2") (pintype "passive"))
    )
    (net (code "49") (name "Net-(D4-Pad1)") (class "Default")
      (node (ref "D4") (pin "1") (pinfunction "1_1") (pintype "passive"))
      (node (ref "R23") (pin "2") (pinfunction "2_2") (pintype "passive"))
    )
    (net (code "50") (name "Net-(J5-Pad2)") (class "Default")
      (node (ref "J5") (pin "2") (pinfunction "2_2") (pintype "passive"))
      (node (ref "R16") (pin "2") (pinfunction "2_2") (pintype "passive"))
    )
    (net (code "51") (name "Net-(J5-Pad5)") (class "Default")
      (node (ref "J5") (pin "5") (pinfunction "5_5") (pintype "passive"))
      (node (ref "R15") (pin "2") (pinfunction "2_2") (pintype "passive"))
    )
    (net (code "52") (name "Net-(J6-Pad3)") (class "Default")
      (node (ref "J6") (pin "3") (pinfunction "3_3") (pintype "passive"))
      (node (ref "R4") (pin "2") (pinfunction "2_2") (pintype "passive"))
    )
    (net (code "53") (name "Net-(J6-Pad4)") (class "Default")
      (node (ref "J6") (pin "4") (pinfunction "4_4") (pintype "passive"))
      (node (ref "R5") (pin "2") (pinfunction "2_2") (pintype "passive"))
    )
    (net (code "54") (name "Net-(U1-EN)") (class "Default")
      (node (ref "C3") (pin "2") (pinfunction "2_2") (pintype "passive"))
      (node (ref "R24") (pin "2") (pinfunction "2_2") (pintype "passive"))
      (node (ref "U1") (pin "1") (pinfunction "VIN_1") (pintype "power_in"))
      (node (ref "U1") (pin "3") (pinfunction "EN_3") (pintype "input"))
    )
    (net (code "55") (name "Net-(U2-RB7)") (class "Default")
      (node (ref "R3") (pin "2") (pinfunction "2_2") (pintype "passive"))
      (node (ref "U2") (pin "10") (pinfunction "RB7_10") (pintype "bidirectional"))
    )
    (net (code "56") (name "Net-(U3-CBUS3)") (class "Default")
      (node (ref "R1") (pin "1") (pinfunction "1_1") (pintype "passive"))
      (node (ref "U3") (pin "14") (pinfunction "CBUS3_14") (pintype "bidirectional"))
    )
    (net (code "57") (name "Net-(U3-CBUS4)") (class "Default")
      (node (ref "R2") (pin "1") (pinfunction "1_1") (pintype "passive"))
      (node (ref "U3") (pin "12") (pinfunction "CBUS4_12") (pintype "bidirectional"))
    )
    (net (code "58") (name "unconnected-(J1-ID-Pad4)") (class "Default")
      (node (ref "J1") (pin "4") (pinfunction "ID_4") (pintype "passive+no_connect"))
    )
    (net (code "59") (name "unconnected-(J2-Pad6)") (class "Default")
      (node (ref "J2") (pin "6") (pinfunction "6_6") (pintype "passive+no_connect"))
    )
    (net (code "60") (name "unconnected-(U1-NC-Pad4)") (class "Default")
      (node (ref "U1") (pin "4") (pinfunction "NC_4") (pintype "input+no_connect"))
    )
    (net (code "61") (name "unconnected-(U3-CBUS0-Pad23)") (class "Default")
      (node (ref "U3") (pin "23") (pinfunction "CBUS0_23") (pintype "bidirectional+no_connect"))
    )
    (net (code "62") (name "unconnected-(U3-CBUS1-Pad22)") (class "Default")
      (node (ref "U3") (pin "22") (pinfunction "CBUS1_22") (pintype "bidirectional+no_connect"))
    )
    (net (code "63") (name "unconnected-(U3-CBUS2-Pad13)") (class "Default")
      (node (ref "U3") (pin "13") (pinfunction "CBUS2_13") (pintype "bidirectional+no_connect"))
    )
    (net (code "64") (name "unconnected-(U3-CTS#-Pad11)") (class "Default")
      (node (ref "U3") (pin "11") (pinfunction "CTS#_11") (pintype "input+no_connect"))
    )
    (net (code "65") (name "unconnected-(U3-DCD#-Pad10)") (class "Default")
      (node (ref "U3") (pin "10") (pinfunction "DCD#_10") (pintype "input+no_connect"))
    )
    (net (code "66") (name "unconnected-(U3-DSR#-Pad9)") (class "Default")
      (node (ref "U3") (pin "9") (pinfunction "DSR#_9") (pintype "input+no_connect"))
    )
    (net (code "67") (name "unconnected-(U3-DTR#-Pad2)") (class "Default")
      (node (ref "U3") (pin "2") (pinfunction "DTR#_2") (pintype "output+no_connect"))
    )
    (net (code "68") (name "unconnected-(U3-NC-Pad8)") (class "Default")
      (node (ref "U3") (pin "8") (pinfunction "NC_8") (pintype "input+no_connect"))
    )
    (net (code "69") (name "unconnected-(U3-NC-Pad24)") (class "Default")
      (node (ref "U3") (pin "24") (pinfunction "NC_24") (pintype "input+no_connect"))
    )
    (net (code "70") (name "unconnected-(U3-OSCI-Pad27)") (class "Default")
      (node (ref "U3") (pin "27") (pinfunction "OSCI_27") (pintype "input+no_connect"))
    )
    (net (code "71") (name "unconnected-(U3-OSCO-Pad28)") (class "Default")
      (node (ref "U3") (pin "28") (pinfunction "OSCO_28") (pintype "output+no_connect"))
    )
    (net (code "72") (name "unconnected-(U3-RESET#-Pad19)") (class "Default")
      (node (ref "U3") (pin "19") (pinfunction "RESET#_19") (pintype "input+no_connect"))
    )
    (net (code "73") (name "unconnected-(U3-RI#-Pad6)") (class "Default")
      (node (ref "U3") (pin "6") (pinfunction "RI#_6") (pintype "input+no_connect"))
    )
    (net (code "74") (name "unconnected-(U3-RTS#-Pad3)") (class "Default")
      (node (ref "U3") (pin "3") (pinfunction "RTS#_3") (pintype "output+no_connect"))
    )
    (net (code "75") (name "unconnected-(U4-AUX1-Pad19)") (class "Default")
      (node (ref "U4") (pin "19") (pinfunction "AUX1_19") (pintype "output+no_connect"))
    )
    (net (code "76") (name "unconnected-(U4-AUX2-Pad20)") (class "Default")
      (node (ref "U4") (pin "20") (pinfunction "AUX2_20") (pintype "output+no_connect"))
    )
    (net (code "77") (name "unconnected-(U4-D1-Pad25)") (class "Default")
      (node (ref "U4") (pin "25") (pinfunction "D1_25") (pintype "bidirectional+no_connect"))
    )
    (net (code "78") (name "unconnected-(U4-D2-Pad26)") (class "Default")
      (node (ref "U4") (pin "26") (pinfunction "D2_26") (pintype "bidirectional+no_connect"))
    )
    (net (code "79") (name "unconnected-(U4-D3-Pad27)") (class "Default")
      (node (ref "U4") (pin "27") (pinfunction "D3_27") (pintype "bidirectional+no_connect"))
    )
    (net (code "80") (name "unconnected-(U4-D4-Pad28)") (class "Default")
      (node (ref "U4") (pin "28") (pinfunction "D4_28") (pintype "bidirectional+no_connect"))
    )
    (net (code "81") (name "unconnected-(U4-EA-Pad32)") (class "Default")
      (node (ref "U4") (pin "32") (pinfunction "EA_32") (pintype "bidirectional+no_connect"))
    )
    (net (code "82") (name "unconnected-(U4-I2C-Pad1)") (class "Default")
      (node (ref "U4") (pin "1") (pinfunction "I2C_1") (pintype "input+no_connect"))
    )
    (net (code "83") (name "unconnected-(U4-MFIN-Pad7)") (class "Default")
      (node (ref "U4") (pin "7") (pinfunction "MFIN_7") (pintype "input+no_connect"))
    )
    (net (code "84") (name "unconnected-(U4-MFOUT-Pad8)") (class "Default")
      (node (ref "U4") (pin "8") (pinfunction "MFOUT_8") (pintype "output+no_connect"))
    )
  )
)
